# SCH_project-number-one_2024-08-02.net
KiCad netlist of a schematic drawn in EasyEDA
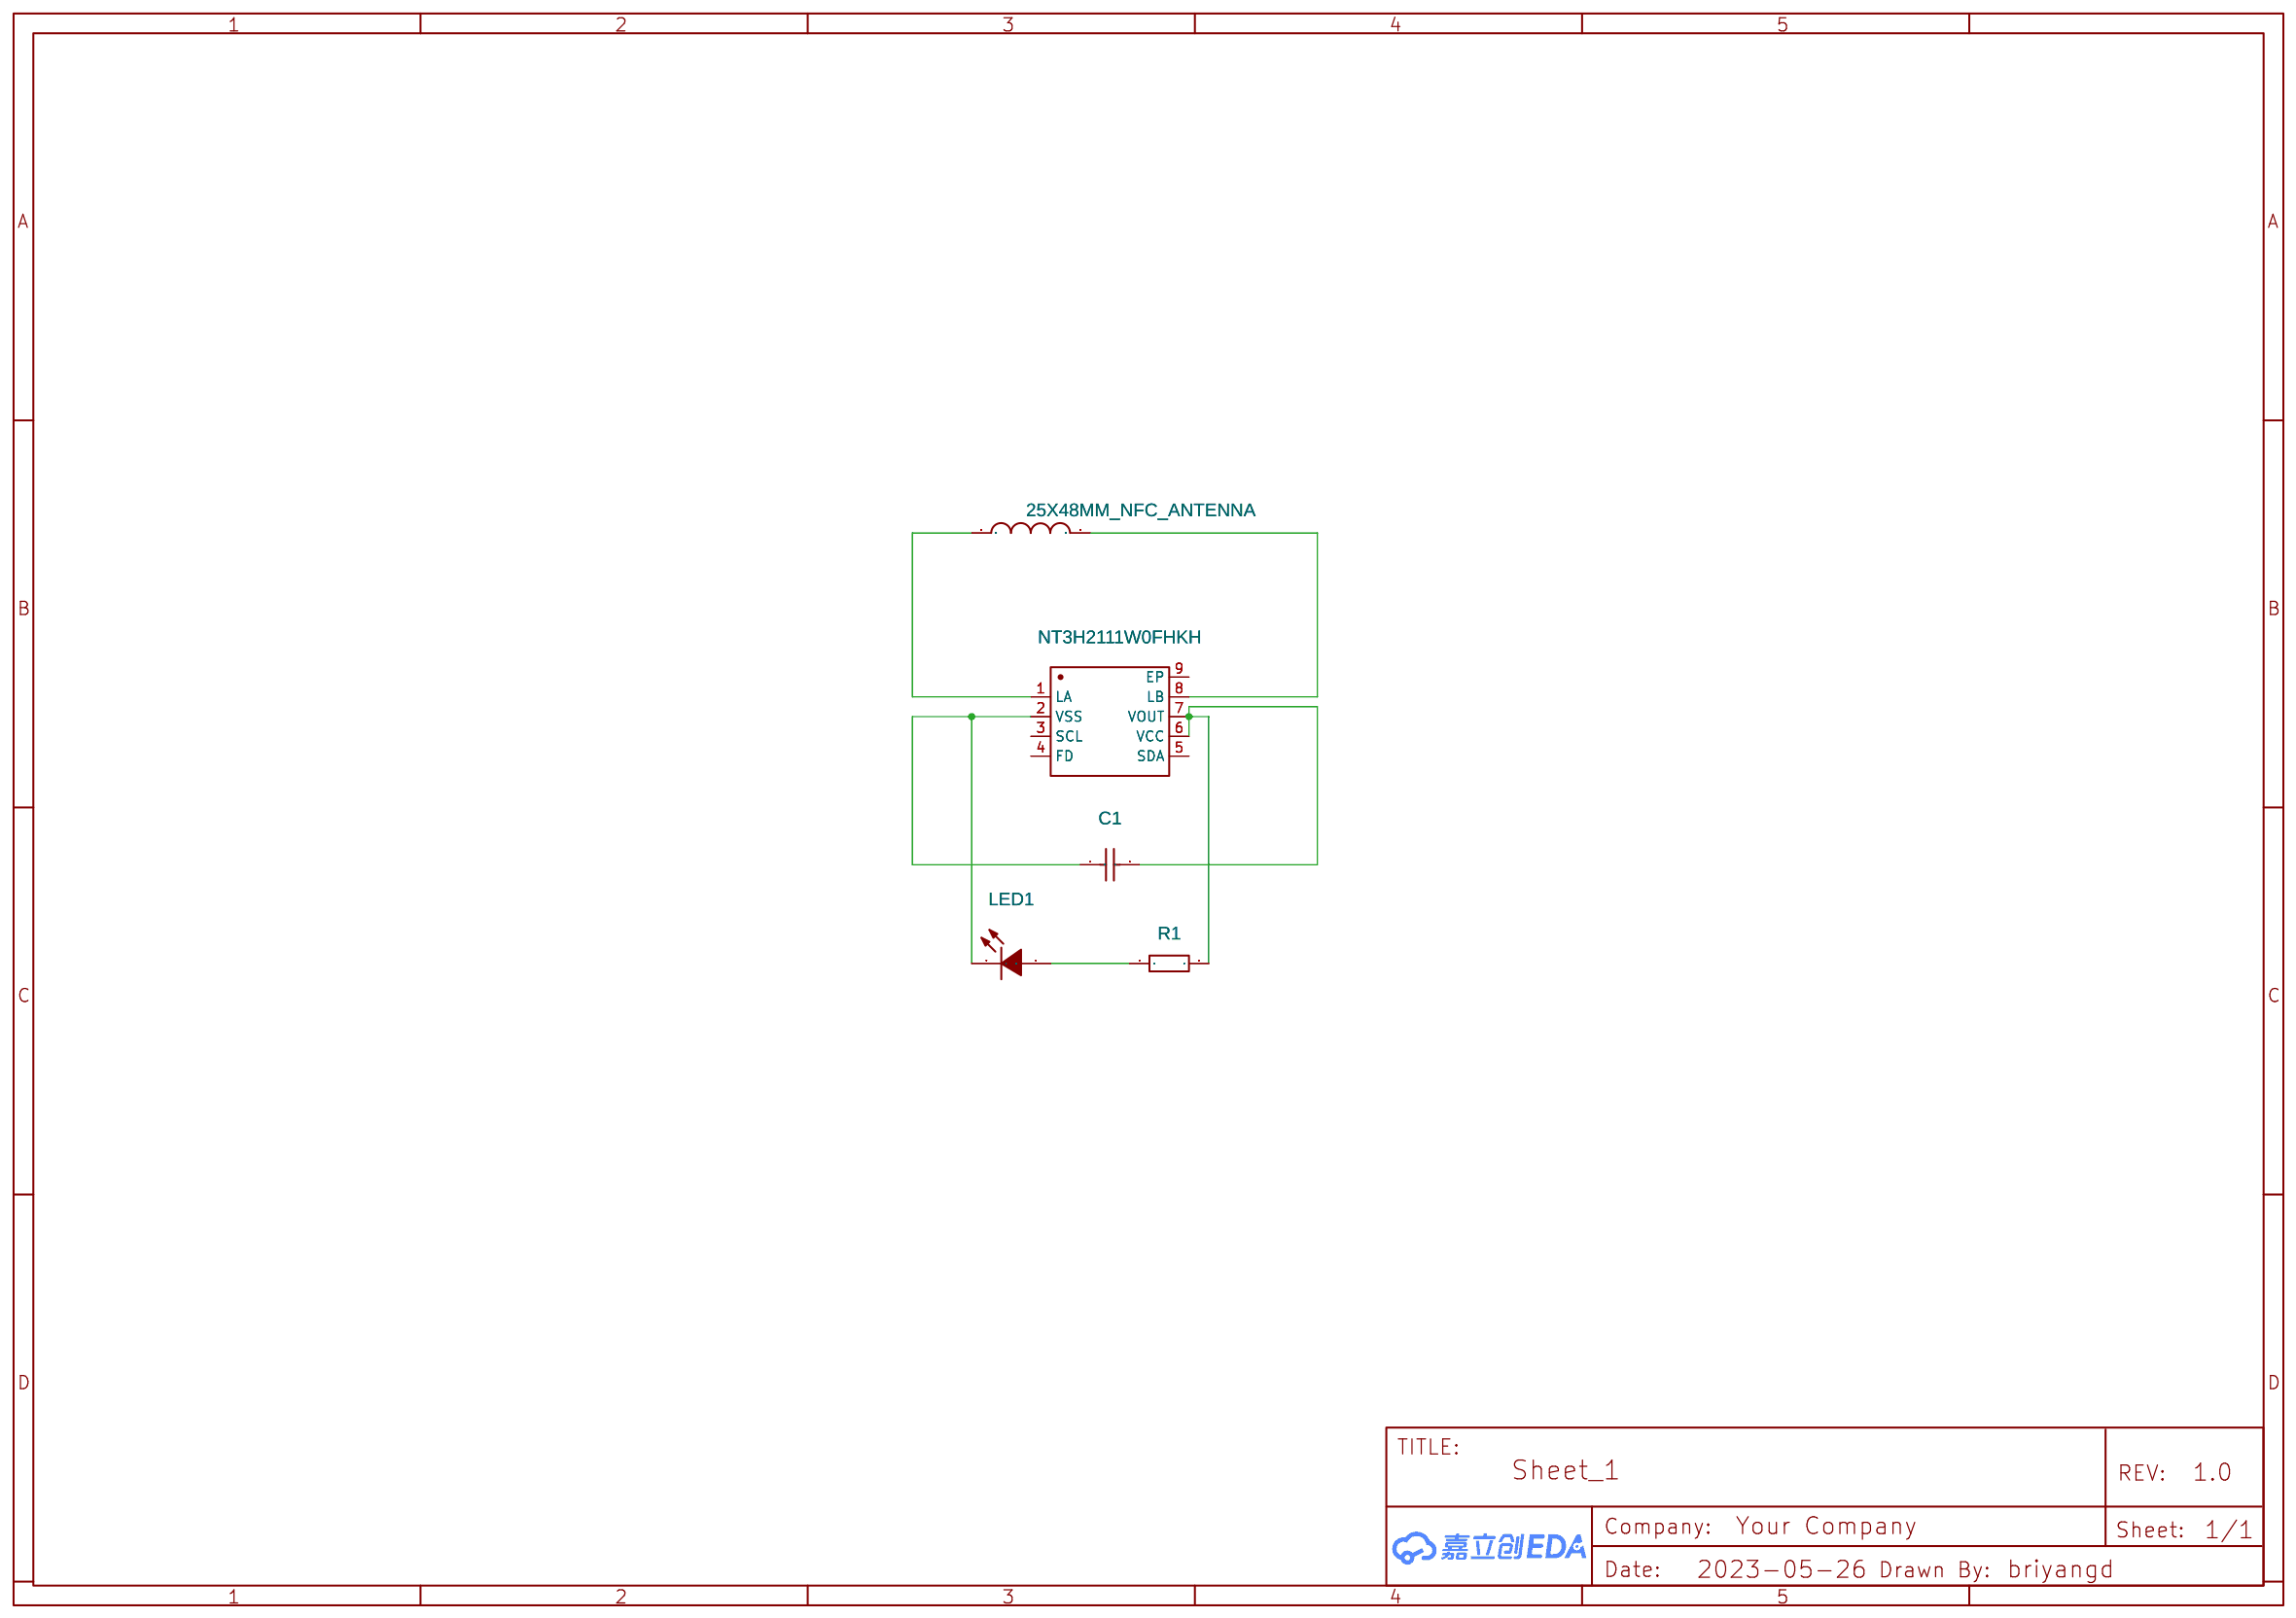
[diagram p0: schematic sheet]

(export (version "E")
  (design (tool "Eeschema 10.0.6"))
  (components
    (comp (ref "1") (value "25X48MM_NFC_ANTENNA") (libsource (lib "") (part "25X48MM_NFC_ANTENNA")))
    (comp (ref "C1")
      (value "220nF")
      (fields (field (name "Manufacturer Part") "CL10B224KA8NNNC") (field (name "Manufacturer") "SAMSUNG"))
      (libsource (lib "") (part "220N CL10B224KA8NNNC"))
    )
    (comp (ref "LED1")
      (value "17-21SUYC/TR8")
      (fields (field (name "Manufacturer Part") "KT-0805黄灯") (field (name "Manufacturer") "KENTO"))
      (libsource (lib "") (part "17-21SUYC/TR8"))
    )
    (comp (ref "R1")
      (value "47Ω")
      (fields
        (field (name "Manufacturer Part") "0603WAF470JT5E")
        (field (name "Manufacturer") "UNI-ROYAL(厚声)")
      )
      (libsource (lib "") (part "0603WAF470JT5E"))
    )
    (comp (ref "U1")
      (value "NT3H2111W0FHKH")
      (fields (field (name "Manufacturer") "NXP(恩智浦)"))
      (libsource (lib "") (part "NT3H2111W0FHKH"))
    )
  )
  (nets
    (net (code "1") (name "Net-(LED1-+)") (class "Default")
      (node (ref "LED1") (pin "1") (pinfunction "+_1") (pintype "unspecified"))
      (node (ref "R1") (pin "1") (pinfunction "1_1") (pintype "input"))
    )
    (net (code "2") (name "Net-(LED1--)") (class "Default")
      (node (ref "C1") (pin "1") (pinfunction "1_1") (pintype "input"))
      (node (ref "LED1") (pin "2") (pinfunction "-_2") (pintype "unspecified"))
      (node (ref "U1") (pin "2") (pinfunction "VSS_2") (pintype "unspecified"))
    )
    (net (code "3") (name "Net-(U1-LA)") (class "Default")
      (node (ref "1") (pin "P$1") (pinfunction "P$1_P$1") (pintype "bidirectional"))
      (node (ref "U1") (pin "1") (pinfunction "LA_1") (pintype "unspecified"))
    )
    (net (code "4") (name "Net-(U1-LB)") (class "Default")
      (node (ref "1") (pin "P$2") (pinfunction "P$2_P$2") (pintype "bidirectional"))
      (node (ref "U1") (pin "8") (pinfunction "LB_8") (pintype "unspecified"))
    )
    (net (code "5") (name "Net-(U1-VCC)") (class "Default")
      (node (ref "C1") (pin "2") (pinfunction "2_2") (pintype "input"))
      (node (ref "R1") (pin "2") (pinfunction "2_2") (pintype "input"))
      (node (ref "U1") (pin "6") (pinfunction "VCC_6") (pintype "unspecified"))
      (node (ref "U1") (pin "7") (pinfunction "VOUT_7") (pintype "unspecified"))
    )
    (net (code "6") (name "unconnected-(U1-EP-Pad9)") (class "Default")
      (node (ref "U1") (pin "9") (pinfunction "EP_9") (pintype "unspecified"))
    )
    (net (code "7") (name "unconnected-(U1-FD-Pad4)") (class "Default")
      (node (ref "U1") (pin "4") (pinfunction "FD_4") (pintype "unspecified"))
    )
    (net (code "8") (name "unconnected-(U1-SCL-Pad3)") (class "Default")
      (node (ref "U1") (pin "3") (pinfunction "SCL_3") (pintype "unspecified"))
    )
    (net (code "9") (name "unconnected-(U1-SDA-Pad5)") (class "Default")
      (node (ref "U1") (pin "5") (pinfunction "SDA_5") (pintype "unspecified"))
    )
  )
)
